# new_board.net
KiCad netlist of a schematic drawn in EAGLE
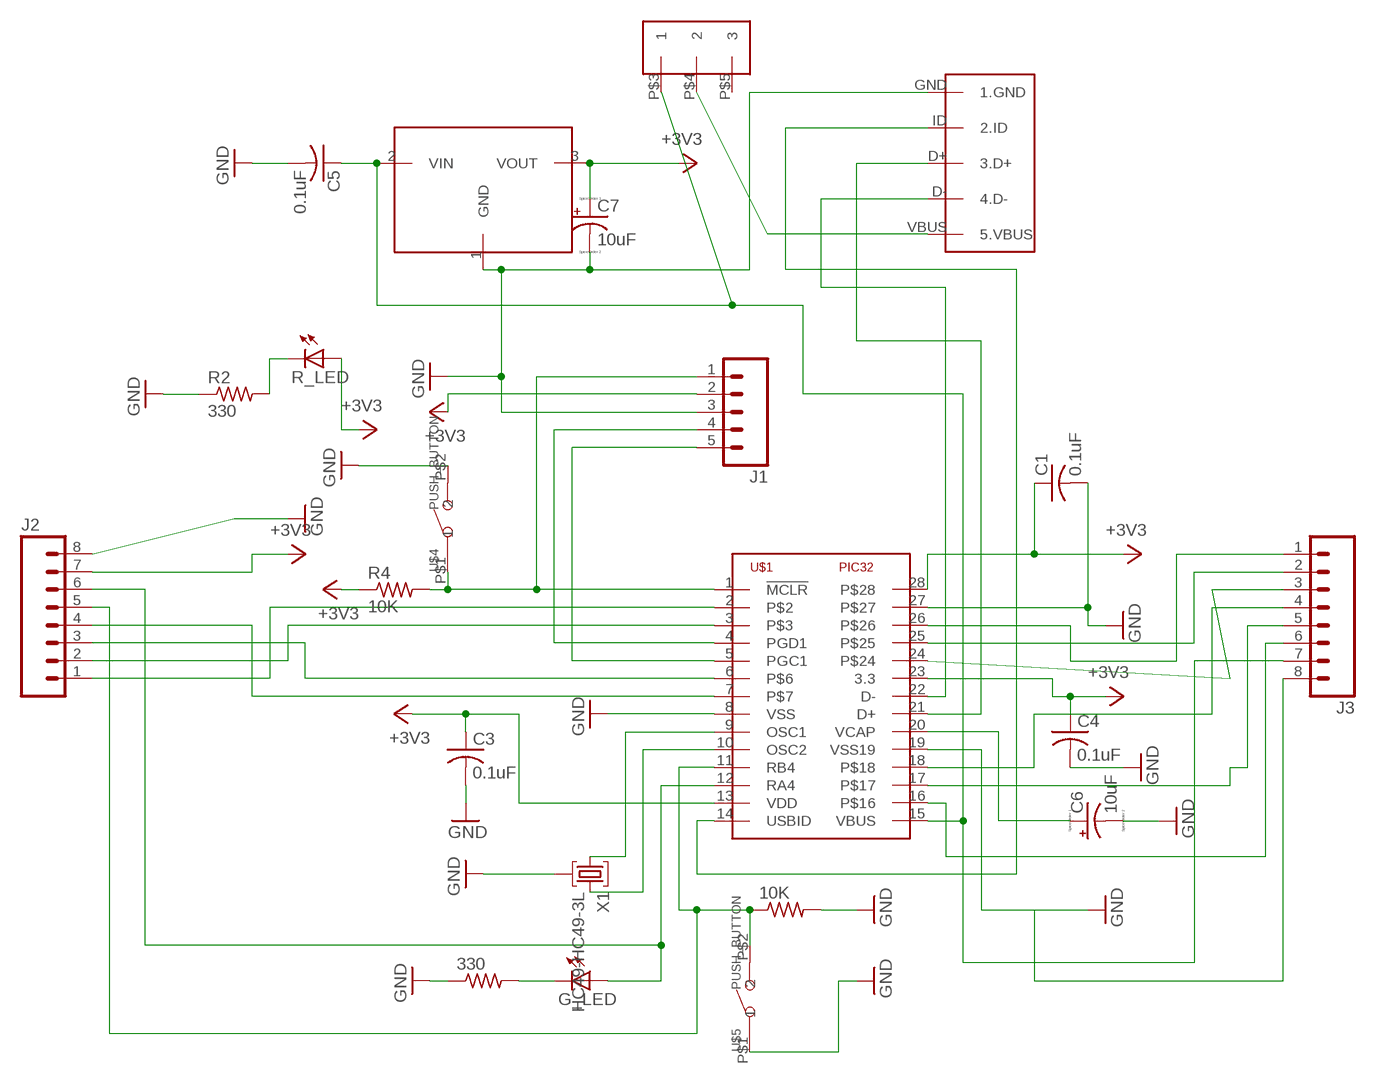
[diagram p0: schematic, sheet 1]

(export (version "E")
  (design (tool "Eeschema 10.0.6"))
  (components
    (comp (ref ".")
      (value "MINI_USB")
      (footprint "eagle-import:USB-MB-H")
      (libsource (lib "eagle-import") (part "MINI_USB"))
    )
    (comp (ref "10K")
      (value "R-US_0207/10")
      (footprint "eagle-import:0207_10")
      (libsource (lib "eagle-import") (part "R-US_0207/10"))
    )
    (comp (ref "330")
      (value "R-US_0207/10")
      (footprint "eagle-import:0207_10")
      (libsource (lib "eagle-import") (part "R-US_0207/10"))
    )
    (comp (ref "C1")
      (value "0.1uF")
      (footprint "eagle-import:C025-025X050")
      (libsource (lib "eagle-import") (part "C-US025-025X050"))
    )
    (comp (ref "C3")
      (value "0.1uF")
      (footprint "eagle-import:C025-025X050")
      (libsource (lib "eagle-import") (part "C-US025-025X050"))
    )
    (comp (ref "C4")
      (value "0.1uF")
      (footprint "eagle-import:C025-025X050")
      (libsource (lib "eagle-import") (part "C-US025-025X050"))
    )
    (comp (ref "C5")
      (value "0.1uF")
      (footprint "eagle-import:C025-025X050")
      (libsource (lib "eagle-import") (part "C-US025-025X050"))
    )
    (comp (ref "C6")
      (value "10uF")
      (footprint "eagle-import:TT2D5")
      (libsource (lib "eagle-import") (part "CPOL-USTT2D5"))
    )
    (comp (ref "C7")
      (value "10uF")
      (footprint "eagle-import:TT2D5")
      (libsource (lib "eagle-import") (part "CPOL-USTT2D5"))
    )
    (comp (ref "G_LED")
      (value "LED3MM")
      (footprint "eagle-import:LED3MM")
      (libsource (lib "eagle-import") (part "LED3MM"))
    )
    (comp (ref "J1")
      (value "M05NO_SILK")
      (footprint "eagle-import:1X05_NO_SILK")
      (libsource (lib "eagle-import") (part "M05NO_SILK"))
    )
    (comp (ref "J2")
      (value "M08")
      (footprint "eagle-import:1X08_ROUND")
      (libsource (lib "eagle-import") (part "M08"))
    )
    (comp (ref "J3")
      (value "M08")
      (footprint "eagle-import:1X08_ROUND")
      (libsource (lib "eagle-import") (part "M08"))
    )
    (comp (ref "R2")
      (value "330")
      (footprint "eagle-import:0207_10")
      (libsource (lib "eagle-import") (part "R-US_0207/10"))
    )
    (comp (ref "R4")
      (value "10K")
      (footprint "eagle-import:0207_10")
      (libsource (lib "eagle-import") (part "R-US_0207/10"))
    )
    (comp (ref "R_LED")
      (value "LED3MM")
      (footprint "eagle-import:LED3MM")
      (libsource (lib "eagle-import") (part "LED3MM"))
    )
    (comp (ref "U$1")
      (value "PIC32")
      (footprint "eagle-import:DIL28-3")
      (libsource (lib "eagle-import") (part "PIC32"))
    )
    (comp (ref "U$3")
      (value "SLIDE_SWITCH")
      (footprint "eagle-import:SLIDE_SWITCH")
      (libsource (lib "eagle-import") (part "SLIDE_SWITCH"))
    )
    (comp (ref "U$4")
      (value "PUSH_BUTTON")
      (footprint "eagle-import:PUSH_BUTTON")
      (libsource (lib "eagle-import") (part "PUSH_BUTTON"))
    )
    (comp (ref "U$5")
      (value "PUSH_BUTTON")
      (footprint "eagle-import:PUSH_BUTTON")
      (libsource (lib "eagle-import") (part "PUSH_BUTTON"))
    )
    (comp (ref "U$9")
      (value "MCP1702")
      (footprint "eagle-import:TO92")
      (libsource (lib "eagle-import") (part "MCP1702"))
    )
    (comp (ref "X1")
      (value "HC49-HC49-3L")
      (footprint "eagle-import:HC49-3L")
      (libsource (lib "eagle-import") (part "HC49-HC49-3L"))
    )
  )
  (nets
    (net (code "1") (name "+3V3") (class "Default")
      (node (ref "C1") (pin "1") (pinfunction "1_1") (pintype "passive"))
      (node (ref "C3") (pin "1") (pinfunction "1_1") (pintype "passive"))
      (node (ref "C4") (pin "1") (pinfunction "1_1") (pintype "passive"))
      (node (ref "C7") (pin "+") (pinfunction "+_+") (pintype "passive"))
      (node (ref "J1") (pin "2") (pinfunction "2_2") (pintype "passive"))
      (node (ref "J2") (pin "7") (pinfunction "7_7") (pintype "passive"))
      (node (ref "R4") (pin "1") (pinfunction "1_1") (pintype "passive"))
      (node (ref "R_LED") (pin "A") (pinfunction "A_A") (pintype "passive"))
      (node (ref "U$1") (pin "13") (pinfunction "VDD_13") (pintype "bidirectional"))
      (node (ref "U$1") (pin "23") (pinfunction "3.3_23") (pintype "bidirectional"))
      (node (ref "U$1") (pin "28") (pinfunction "P$28_28") (pintype "bidirectional"))
      (node (ref "U$9") (pin "3") (pinfunction "VOUT_3") (pintype "bidirectional"))
    )
    (net (code "2") (name "GND") (class "Default")
      (node (ref ".") (pin "GND") (pinfunction "1.GND_GND") (pintype "bidirectional"))
      (node (ref "10K") (pin "2") (pinfunction "2_2") (pintype "passive"))
      (node (ref "330") (pin "1") (pinfunction "1_1") (pintype "passive"))
      (node (ref "C1") (pin "2") (pinfunction "2_2") (pintype "passive"))
      (node (ref "C3") (pin "2") (pinfunction "2_2") (pintype "passive"))
      (node (ref "C4") (pin "2") (pinfunction "2_2") (pintype "passive"))
      (node (ref "C5") (pin "2") (pinfunction "2_2") (pintype "passive"))
      (node (ref "C6") (pin "-") (pinfunction "-_-") (pintype "passive"))
      (node (ref "C7") (pin "-") (pinfunction "-_-") (pintype "passive"))
      (node (ref "J1") (pin "3") (pinfunction "3_3") (pintype "passive"))
      (node (ref "J2") (pin "8") (pinfunction "8_8") (pintype "passive"))
      (node (ref "J3") (pin "8") (pinfunction "8_8") (pintype "passive"))
      (node (ref "R2") (pin "1") (pinfunction "1_1") (pintype "passive"))
      (node (ref "U$1") (pin "19") (pinfunction "VSS19_19") (pintype "bidirectional"))
      (node (ref "U$1") (pin "27") (pinfunction "P$27_27") (pintype "bidirectional"))
      (node (ref "U$1") (pin "8") (pinfunction "VSS_8") (pintype "bidirectional"))
      (node (ref "U$4") (pin "P$2") (pinfunction "2_P$2") (pintype "bidirectional"))
      (node (ref "U$5") (pin "P$1") (pinfunction "1_P$1") (pintype "bidirectional"))
      (node (ref "U$9") (pin "1") (pinfunction "GND_1") (pintype "bidirectional"))
      (node (ref "X1") (pin "2") (pinfunction "2_2") (pintype "passive"))
    )
    (net (code "3") (name "Net-(.-2.ID)") (class "Default")
      (node (ref ".") (pin "ID") (pinfunction "2.ID_ID") (pintype "bidirectional"))
      (node (ref "U$1") (pin "14") (pinfunction "USBID_14") (pintype "bidirectional"))
    )
    (net (code "4") (name "Net-(.-3.D+)") (class "Default")
      (node (ref ".") (pin "D+") (pinfunction "3.D+_D+") (pintype "bidirectional"))
      (node (ref "U$1") (pin "21") (pinfunction "D+_21") (pintype "bidirectional"))
    )
    (net (code "5") (name "Net-(.-4.D-)") (class "Default")
      (node (ref ".") (pin "D-") (pinfunction "4.D-_D-") (pintype "bidirectional"))
      (node (ref "U$1") (pin "22") (pinfunction "D-_22") (pintype "bidirectional"))
    )
    (net (code "6") (name "Net-(.-5.VBUS)") (class "Default")
      (node (ref ".") (pin "VBUS") (pinfunction "5.VBUS_VBUS") (pintype "bidirectional"))
      (node (ref "U$3") (pin "P$4") (pinfunction "2_P$4") (pintype "bidirectional"))
    )
    (net (code "7") (name "Net-(G_LED-C)") (class "Default")
      (node (ref "330") (pin "2") (pinfunction "2_2") (pintype "passive"))
      (node (ref "G_LED") (pin "K") (pinfunction "C_K") (pintype "passive"))
    )
    (net (code "8") (name "Net-(R_LED-C)") (class "Default")
      (node (ref "R2") (pin "2") (pinfunction "2_2") (pintype "passive"))
      (node (ref "R_LED") (pin "K") (pinfunction "C_K") (pintype "passive"))
    )
    (net (code "9") (name "Net-(U$1-OSC1)") (class "Default")
      (node (ref "U$1") (pin "9") (pinfunction "OSC1_9") (pintype "bidirectional"))
      (node (ref "X1") (pin "1") (pinfunction "1_1") (pintype "passive"))
    )
    (net (code "10") (name "Net-(U$1-OSC2)") (class "Default")
      (node (ref "U$1") (pin "10") (pinfunction "OSC2_10") (pintype "bidirectional"))
      (node (ref "X1") (pin "3") (pinfunction "3_3") (pintype "passive"))
    )
    (net (code "11") (name "Net-(U$1-P$2)") (class "Default")
      (node (ref "J2") (pin "1") (pinfunction "1_1") (pintype "passive"))
      (node (ref "U$1") (pin "2") (pinfunction "P$2_2") (pintype "bidirectional"))
    )
    (net (code "12") (name "Net-(U$1-P$3)") (class "Default")
      (node (ref "J2") (pin "2") (pinfunction "2_2") (pintype "passive"))
      (node (ref "U$1") (pin "3") (pinfunction "P$3_3") (pintype "bidirectional"))
    )
    (net (code "13") (name "Net-(U$1-P$6)") (class "Default")
      (node (ref "J2") (pin "3") (pinfunction "3_3") (pintype "passive"))
      (node (ref "U$1") (pin "6") (pinfunction "P$6_6") (pintype "bidirectional"))
    )
    (net (code "14") (name "Net-(U$1-P$7)") (class "Default")
      (node (ref "J2") (pin "4") (pinfunction "4_4") (pintype "passive"))
      (node (ref "U$1") (pin "7") (pinfunction "P$7_7") (pintype "bidirectional"))
    )
    (net (code "15") (name "Net-(U$1-P$16)") (class "Default")
      (node (ref "J3") (pin "6") (pinfunction "6_6") (pintype "passive"))
      (node (ref "U$1") (pin "16") (pinfunction "P$16_16") (pintype "bidirectional"))
    )
    (net (code "16") (name "Net-(U$1-P$17)") (class "Default")
      (node (ref "J3") (pin "5") (pinfunction "5_5") (pintype "passive"))
      (node (ref "U$1") (pin "17") (pinfunction "P$17_17") (pintype "bidirectional"))
    )
    (net (code "17") (name "Net-(U$1-P$18)") (class "Default")
      (node (ref "J3") (pin "4") (pinfunction "4_4") (pintype "passive"))
      (node (ref "U$1") (pin "18") (pinfunction "P$18_18") (pintype "bidirectional"))
    )
    (net (code "18") (name "Net-(U$1-P$24)") (class "Default")
      (node (ref "J3") (pin "3") (pinfunction "3_3") (pintype "passive"))
      (node (ref "U$1") (pin "24") (pinfunction "P$24_24") (pintype "bidirectional"))
    )
    (net (code "19") (name "Net-(U$1-P$25)") (class "Default")
      (node (ref "J3") (pin "2") (pinfunction "2_2") (pintype "passive"))
      (node (ref "U$1") (pin "25") (pinfunction "P$25_25") (pintype "bidirectional"))
    )
    (net (code "20") (name "Net-(U$1-P$26)") (class "Default")
      (node (ref "J3") (pin "1") (pinfunction "1_1") (pintype "passive"))
      (node (ref "U$1") (pin "26") (pinfunction "P$26_26") (pintype "bidirectional"))
    )
    (net (code "21") (name "Net-(U$1-PGC1)") (class "Default")
      (node (ref "J1") (pin "5") (pinfunction "5_5") (pintype "passive"))
      (node (ref "U$1") (pin "5") (pinfunction "PGC1_5") (pintype "bidirectional"))
    )
    (net (code "22") (name "Net-(U$1-PGD1)") (class "Default")
      (node (ref "J1") (pin "4") (pinfunction "4_4") (pintype "passive"))
      (node (ref "U$1") (pin "4") (pinfunction "PGD1_4") (pintype "bidirectional"))
    )
    (net (code "23") (name "Net-(U$1-RA4)") (class "Default")
      (node (ref "G_LED") (pin "A") (pinfunction "A_A") (pintype "passive"))
      (node (ref "J2") (pin "6") (pinfunction "6_6") (pintype "passive"))
      (node (ref "U$1") (pin "12") (pinfunction "RA4_12") (pintype "bidirectional"))
    )
    (net (code "24") (name "Net-(U$1-RB4)") (class "Default")
      (node (ref "10K") (pin "1") (pinfunction "1_1") (pintype "passive"))
      (node (ref "J2") (pin "5") (pinfunction "5_5") (pintype "passive"))
      (node (ref "U$1") (pin "11") (pinfunction "RB4_11") (pintype "bidirectional"))
      (node (ref "U$5") (pin "P$2") (pinfunction "2_P$2") (pintype "bidirectional"))
    )
    (net (code "25") (name "Net-(U$1-VBUS)") (class "Default")
      (node (ref "C5") (pin "1") (pinfunction "1_1") (pintype "passive"))
      (node (ref "J3") (pin "7") (pinfunction "7_7") (pintype "passive"))
      (node (ref "U$1") (pin "15") (pinfunction "VBUS_15") (pintype "bidirectional"))
      (node (ref "U$3") (pin "P$3") (pinfunction "1_P$3") (pintype "bidirectional"))
      (node (ref "U$9") (pin "2") (pinfunction "VIN_2") (pintype "bidirectional"))
    )
    (net (code "26") (name "Net-(U$1-VCAP)") (class "Default")
      (node (ref "C6") (pin "+") (pinfunction "+_+") (pintype "passive"))
      (node (ref "U$1") (pin "20") (pinfunction "VCAP_20") (pintype "bidirectional"))
    )
    (net (code "27") (name "Net-(U$1-~{MCLR})") (class "Default")
      (node (ref "J1") (pin "1") (pinfunction "1_1") (pintype "passive"))
      (node (ref "R4") (pin "2") (pinfunction "2_2") (pintype "passive"))
      (node (ref "U$1") (pin "1") (pinfunction "~{MCLR}_1") (pintype "bidirectional"))
      (node (ref "U$4") (pin "P$1") (pinfunction "1_P$1") (pintype "bidirectional"))
    )
    (net (code "28") (name "unconnected-(U$3-3-PadP$5)") (class "Default")
      (node (ref "U$3") (pin "P$5") (pinfunction "3_P$5") (pintype "bidirectional"))
    )
  )
)
